# SCH_RMB-Frankenboard_2024-09-02.net
KiCad netlist of a schematic drawn in EasyEDA
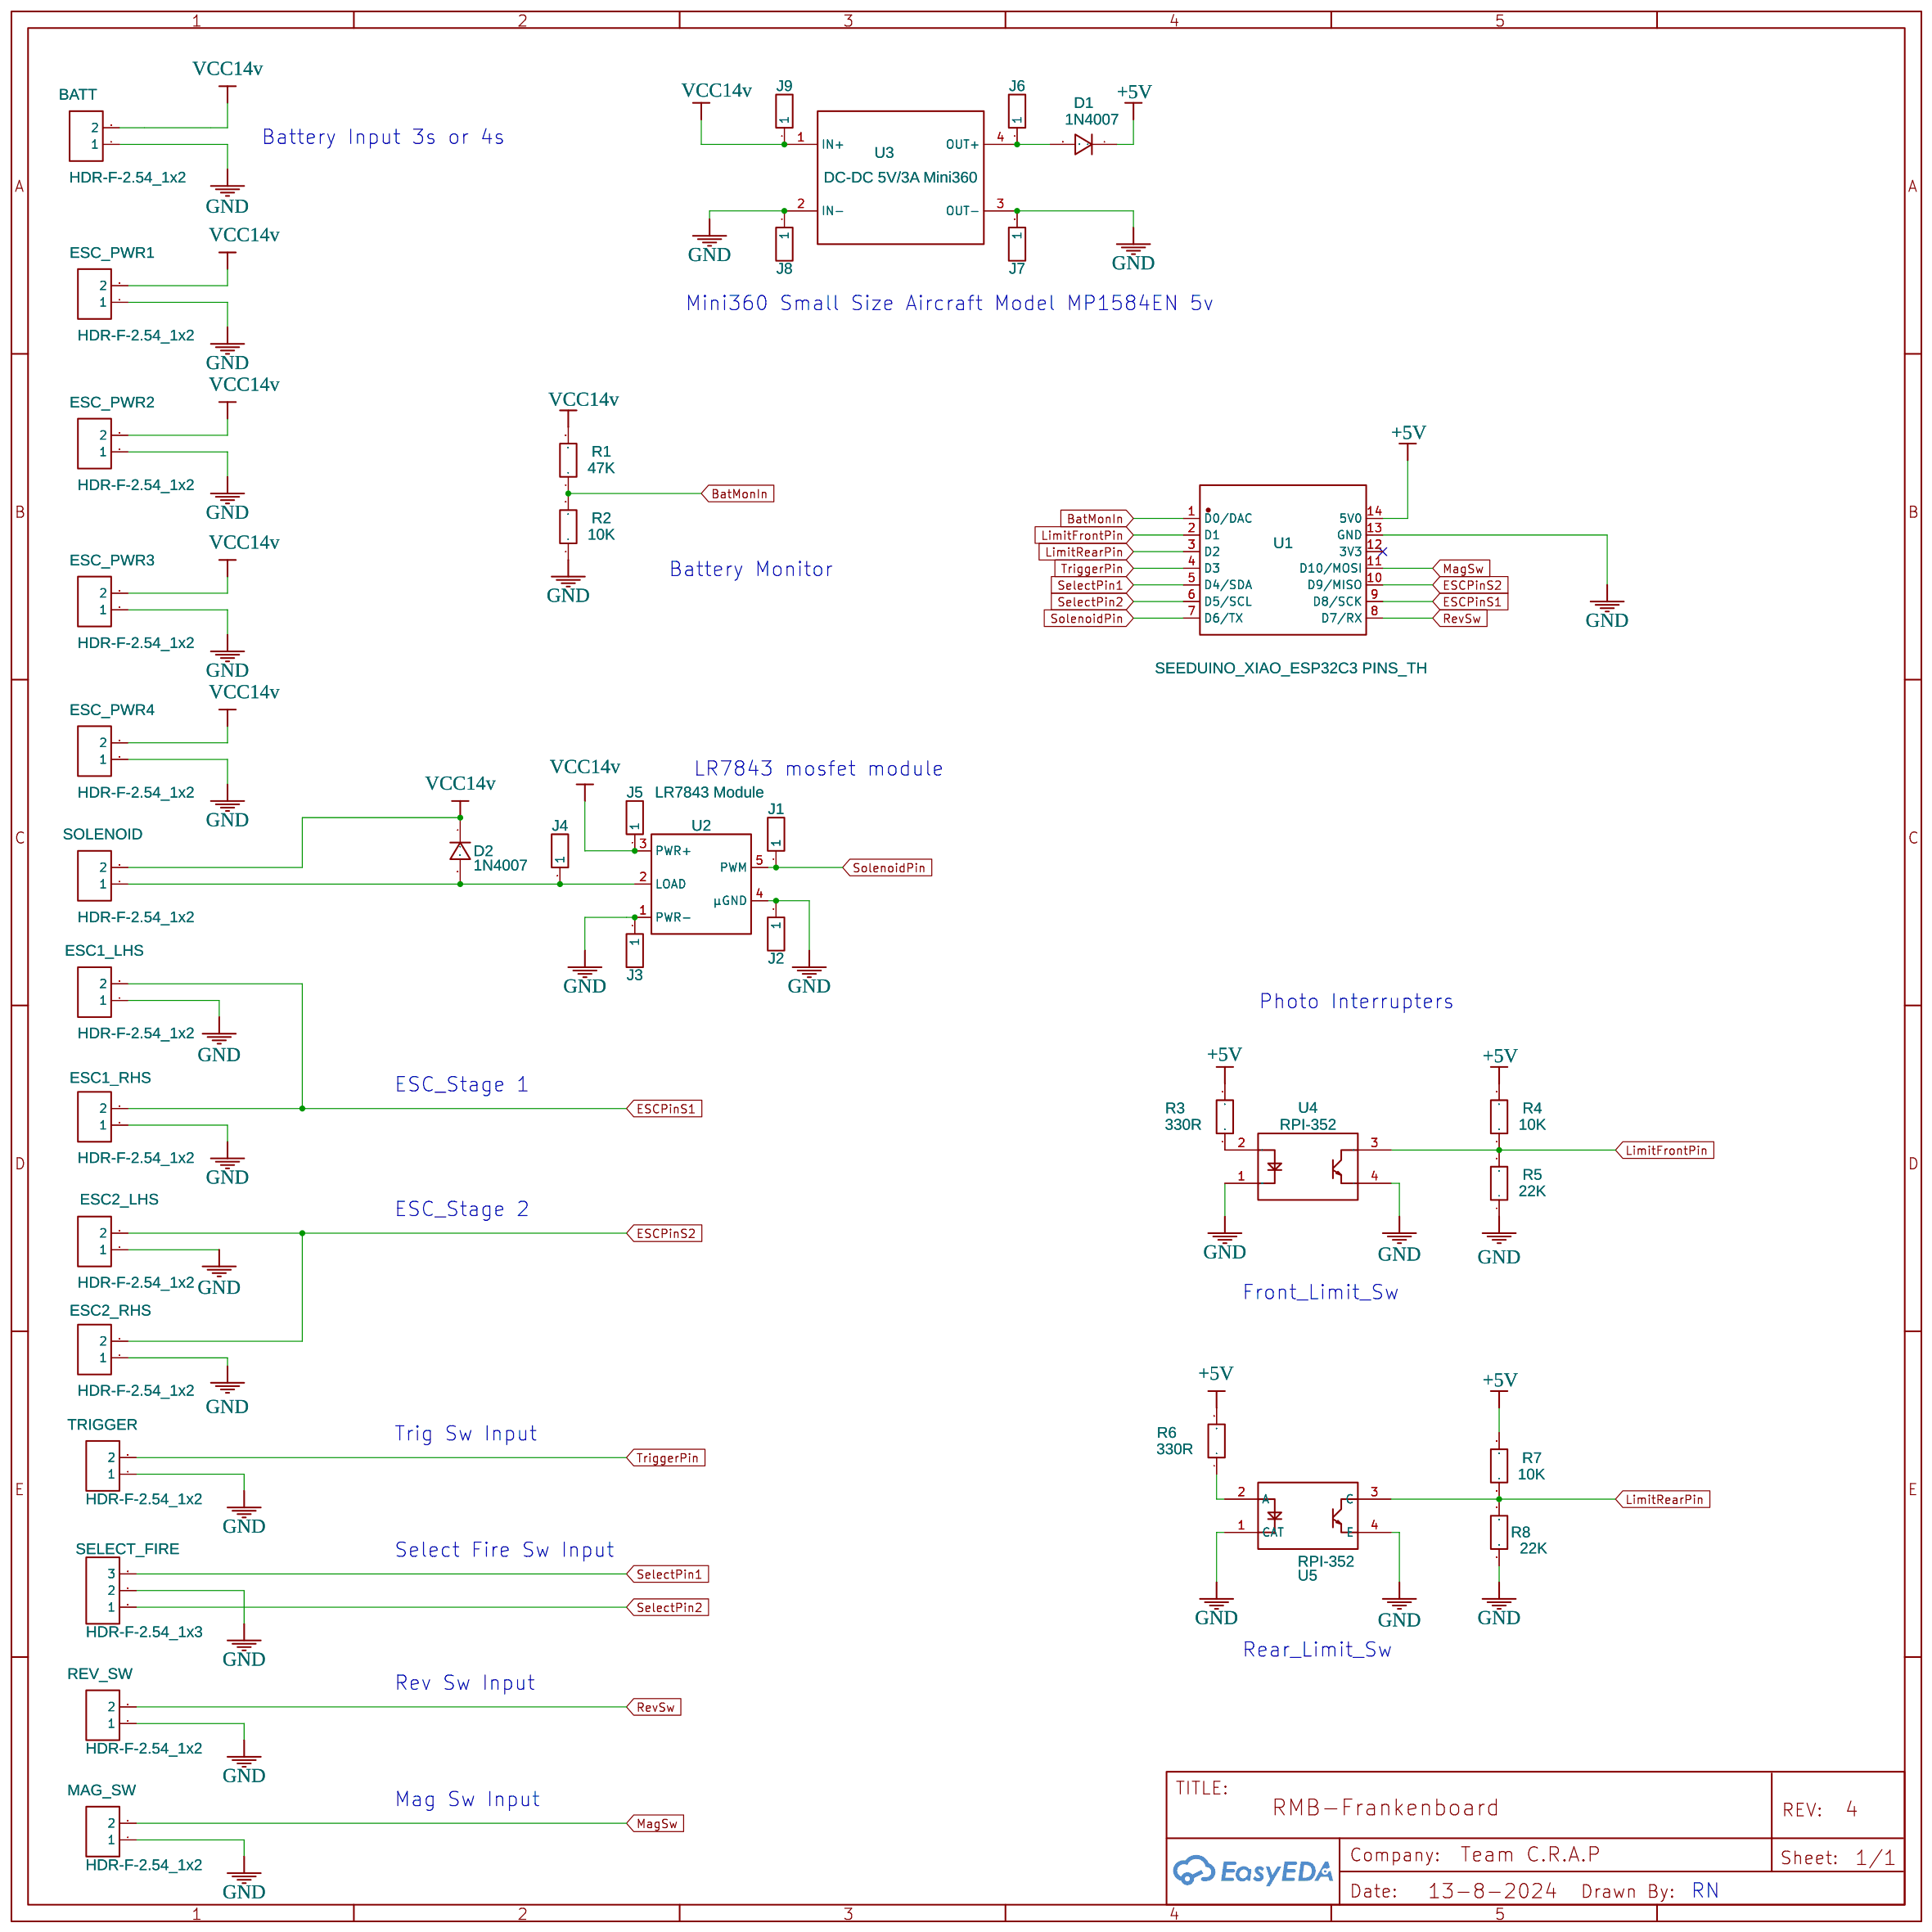
[diagram p0: schematic sheet]

(export (version "E")
  (design (tool "Eeschema 10.0.6"))
  (components
    (comp (ref "BATT") (value "HDR-F-2.54_1x2") (libsource (lib "") (part "HDR-F-2.54_1x2_2")))
    (comp (ref "D1")
      (value "1N4007")
      (fields (field (name "Manufacturer") "SEMTECH"))
      (libsource (lib "") (part "1N4007"))
    )
    (comp (ref "D2")
      (value "1N4007")
      (fields (field (name "Manufacturer") "SEMTECH"))
      (libsource (lib "") (part "1N4007_1"))
    )
    (comp (ref "ESC1_LHS") (value "HDR-F-2.54_1x2") (libsource (lib "") (part "HDR-F-2.54_1x2")))
    (comp (ref "ESC1_RHS") (value "HDR-F-2.54_1x2") (libsource (lib "") (part "HDR-F-2.54_1x2_9")))
    (comp (ref "ESC2_LHS") (value "HDR-F-2.54_1x2") (libsource (lib "") (part "HDR-F-2.54_1x2_7")))
    (comp (ref "ESC2_RHS") (value "HDR-F-2.54_1x2") (libsource (lib "") (part "HDR-F-2.54_1x2_8")))
    (comp (ref "ESC_PWR1") (value "HDR-F-2.54_1x2") (libsource (lib "") (part "HDR-F-2.54_1x2_4")))
    (comp (ref "ESC_PWR2") (value "HDR-F-2.54_1x2") (libsource (lib "") (part "HDR-F-2.54_1x2_4")))
    (comp (ref "ESC_PWR3") (value "HDR-F-2.54_1x2") (libsource (lib "") (part "HDR-F-2.54_1x2_4")))
    (comp (ref "ESC_PWR4") (value "HDR-F-2.54_1x2") (libsource (lib "") (part "HDR-F-2.54_1x2_4")))
    (comp (ref "J1") (value "HDR-M-2.54_1x1") (libsource (lib "") (part "HDR-M-2.54_1x1_1")))
    (comp (ref "J2") (value "HDR-M-2.54_1x1") (libsource (lib "") (part "HDR-M-2.54_1x1")))
    (comp (ref "J3") (value "HDR-M-2.54_1x1") (libsource (lib "") (part "HDR-M-2.54_1x1")))
    (comp (ref "J4") (value "HDR-M-2.54_1x1") (libsource (lib "") (part "HDR-M-2.54_1x1_1")))
    (comp (ref "J5") (value "HDR-M-2.54_1x1") (libsource (lib "") (part "HDR-M-2.54_1x1_1")))
    (comp (ref "J6") (value "HDR-M-2.54_1x1") (libsource (lib "") (part "HDR-M-2.54_1x1_1")))
    (comp (ref "J7") (value "HDR-M-2.54_1x1") (libsource (lib "") (part "HDR-M-2.54_1x1")))
    (comp (ref "J8") (value "HDR-M-2.54_1x1") (libsource (lib "") (part "HDR-M-2.54_1x1")))
    (comp (ref "J9") (value "HDR-M-2.54_1x1") (libsource (lib "") (part "HDR-M-2.54_1x1_1")))
    (comp (ref "MAG_SW") (value "HDR-F-2.54_1x2") (libsource (lib "") (part "HDR-F-2.54_1x2_6")))
    (comp (ref "R1") (value "47K") (libsource (lib "") (part "R_AXIAL-0.3_EU")))
    (comp (ref "R2") (value "10K") (libsource (lib "") (part "R_AXIAL-0.3_EU")))
    (comp (ref "R3") (value "330R") (libsource (lib "") (part "R_AXIAL-0.3_EU")))
    (comp (ref "R4") (value "10K") (libsource (lib "") (part "R_0603_EU")))
    (comp (ref "R5") (value "22K") (libsource (lib "") (part "R_0603_EU")))
    (comp (ref "R6") (value "330R") (libsource (lib "") (part "R_AXIAL-0.3_EU")))
    (comp (ref "R7") (value "10K") (libsource (lib "") (part "R_0603_EU")))
    (comp (ref "R8") (value "22K") (libsource (lib "") (part "R_0603_EU")))
    (comp (ref "REV_SW") (value "HDR-F-2.54_1x2") (libsource (lib "") (part "HDR-F-2.54_1x2_3")))
    (comp (ref "SELECT_FIRE") (value "HDR-F-2.54_1x3") (libsource (lib "") (part "HDR-F-2.54_1x3")))
    (comp (ref "SOLENOID") (value "HDR-F-2.54_1x2") (libsource (lib "") (part "HDR-F-2.54_1x2_1")))
    (comp (ref "TRIGGER") (value "HDR-F-2.54_1x2") (libsource (lib "") (part "HDR-F-2.54_1x2_5")))
    (comp (ref "U1")
      (value "SEEDUINO_XIAO_ESP32C3 PINS_TH")
      (libsource (lib "") (part "SEEDUINO_XIAO_ESP32C3 PINS_TH"))
    )
    (comp (ref "U2") (value "LR7843 Module") (libsource (lib "") (part "LR7843 Module")))
    (comp (ref "U3")
      (value "DC-DC 5V/3A Mini360")
      (fields
        (field (name "Manufacturer Part") "Aircraft Model MP1584EN Power Module")
        (field (name "Manufacturer") "Generic")
      )
      (libsource (lib "") (part "DC-DC 5V/3A Mini360"))
    )
    (comp (ref "U4")
      (value "RPI-352")
      (fields (field (name "Manufacturer") "ROHM(罗姆)"))
      (libsource (lib "") (part "RPI-352"))
    )
    (comp (ref "U5")
      (value "RPI-352")
      (fields (field (name "Manufacturer") "ROHM(罗姆)"))
      (libsource (lib "") (part "RPI-352"))
    )
  )
  (nets
    (net (code "1") (name "+5V") (class "Default")
      (node (ref "D1") (pin "1") (pinfunction "1_1") (pintype "unspecified"))
      (node (ref "R3") (pin "2") (pinfunction "2_2") (pintype "unspecified"))
      (node (ref "R4") (pin "2") (pinfunction "2_2") (pintype "unspecified"))
      (node (ref "R6") (pin "2") (pinfunction "2_2") (pintype "unspecified"))
      (node (ref "R7") (pin "2") (pinfunction "2_2") (pintype "unspecified"))
      (node (ref "U1") (pin "14") (pinfunction "5V0_14") (pintype "unspecified"))
    )
    (net (code "2") (name "BatMonIn") (class "Default")
      (node (ref "R1") (pin "1") (pinfunction "1_1") (pintype "unspecified"))
      (node (ref "R2") (pin "2") (pinfunction "2_2") (pintype "unspecified"))
      (node (ref "U1") (pin "1") (pinfunction "D0/DAC_1") (pintype "unspecified"))
    )
    (net (code "3") (name "ESCPinS1") (class "Default")
      (node (ref "ESC1_LHS") (pin "2") (pinfunction "2_2") (pintype "input"))
      (node (ref "ESC1_RHS") (pin "2") (pinfunction "2_2") (pintype "input"))
      (node (ref "U1") (pin "9") (pinfunction "D8/SCK_9") (pintype "unspecified"))
    )
    (net (code "4") (name "ESCPinS2") (class "Default")
      (node (ref "ESC2_LHS") (pin "2") (pinfunction "2_2") (pintype "input"))
      (node (ref "ESC2_RHS") (pin "2") (pinfunction "2_2") (pintype "input"))
      (node (ref "U1") (pin "10") (pinfunction "D9/MISO_10") (pintype "unspecified"))
    )
    (net (code "5") (name "GND") (class "Default")
      (node (ref "BATT") (pin "1") (pinfunction "1_1") (pintype "input"))
      (node (ref "ESC1_LHS") (pin "1") (pinfunction "1_1") (pintype "input"))
      (node (ref "ESC1_RHS") (pin "1") (pinfunction "1_1") (pintype "input"))
      (node (ref "ESC2_LHS") (pin "1") (pinfunction "1_1") (pintype "input"))
      (node (ref "ESC2_RHS") (pin "1") (pinfunction "1_1") (pintype "input"))
      (node (ref "ESC_PWR1") (pin "1") (pinfunction "1_1") (pintype "input"))
      (node (ref "ESC_PWR2") (pin "1") (pinfunction "1_1") (pintype "input"))
      (node (ref "ESC_PWR3") (pin "1") (pinfunction "1_1") (pintype "input"))
      (node (ref "ESC_PWR4") (pin "1") (pinfunction "1_1") (pintype "input"))
      (node (ref "J2") (pin "1") (pinfunction "1_1") (pintype "input"))
      (node (ref "J3") (pin "1") (pinfunction "1_1") (pintype "input"))
      (node (ref "J7") (pin "1") (pinfunction "1_1") (pintype "input"))
      (node (ref "J8") (pin "1") (pinfunction "1_1") (pintype "input"))
      (node (ref "MAG_SW") (pin "1") (pinfunction "1_1") (pintype "input"))
      (node (ref "R2") (pin "1") (pinfunction "1_1") (pintype "unspecified"))
      (node (ref "R5") (pin "1") (pinfunction "1_1") (pintype "unspecified"))
      (node (ref "R8") (pin "1") (pinfunction "1_1") (pintype "unspecified"))
      (node (ref "REV_SW") (pin "1") (pinfunction "1_1") (pintype "input"))
      (node (ref "SELECT_FIRE") (pin "2") (pinfunction "2_2") (pintype "input"))
      (node (ref "TRIGGER") (pin "1") (pinfunction "1_1") (pintype "input"))
      (node (ref "U1") (pin "13") (pinfunction "GND_13") (pintype "unspecified"))
      (node (ref "U2") (pin "1") (pinfunction "PWR-_1") (pintype "unspecified"))
      (node (ref "U2") (pin "4") (pinfunction "μGND_4") (pintype "unspecified"))
      (node (ref "U3") (pin "2") (pinfunction "IN-_2") (pintype "unspecified"))
      (node (ref "U3") (pin "3") (pinfunction "OUT-_3") (pintype "unspecified"))
      (node (ref "U4") (pin "1") (pinfunction "CAT_1") (pintype "unspecified"))
      (node (ref "U4") (pin "4") (pinfunction "E_4") (pintype "unspecified"))
      (node (ref "U5") (pin "1") (pinfunction "CAT_1") (pintype "unspecified"))
      (node (ref "U5") (pin "4") (pinfunction "E_4") (pintype "unspecified"))
    )
    (net (code "6") (name "LimitFrontPin") (class "Default")
      (node (ref "R4") (pin "1") (pinfunction "1_1") (pintype "unspecified"))
      (node (ref "R5") (pin "2") (pinfunction "2_2") (pintype "unspecified"))
      (node (ref "U1") (pin "2") (pinfunction "D1_2") (pintype "unspecified"))
      (node (ref "U4") (pin "3") (pinfunction "C_3") (pintype "unspecified"))
    )
    (net (code "7") (name "LimitRearPin") (class "Default")
      (node (ref "R7") (pin "1") (pinfunction "1_1") (pintype "unspecified"))
      (node (ref "R8") (pin "2") (pinfunction "2_2") (pintype "unspecified"))
      (node (ref "U1") (pin "3") (pinfunction "D2_3") (pintype "unspecified"))
      (node (ref "U5") (pin "3") (pinfunction "C_3") (pintype "unspecified"))
    )
    (net (code "8") (name "MagSw") (class "Default")
      (node (ref "MAG_SW") (pin "2") (pinfunction "2_2") (pintype "input"))
      (node (ref "U1") (pin "11") (pinfunction "D10/MOSI_11") (pintype "unspecified"))
    )
    (net (code "9") (name "Net-(U2-LOAD)") (class "Default")
      (node (ref "D2") (pin "2") (pinfunction "2_2") (pintype "unspecified"))
      (node (ref "J4") (pin "1") (pinfunction "1_1") (pintype "input"))
      (node (ref "SOLENOID") (pin "1") (pinfunction "1_1") (pintype "input"))
      (node (ref "U2") (pin "2") (pinfunction "LOAD_2") (pintype "unspecified"))
    )
    (net (code "10") (name "Net-(U3-OUT+)") (class "Default")
      (node (ref "D1") (pin "2") (pinfunction "2_2") (pintype "unspecified"))
      (node (ref "J6") (pin "1") (pinfunction "1_1") (pintype "input"))
      (node (ref "U3") (pin "4") (pinfunction "OUT+_4") (pintype "unspecified"))
    )
    (net (code "11") (name "Net-(U4-A)") (class "Default")
      (node (ref "R3") (pin "1") (pinfunction "1_1") (pintype "unspecified"))
      (node (ref "U4") (pin "2") (pinfunction "A_2") (pintype "unspecified"))
    )
    (net (code "12") (name "Net-(U5-A)") (class "Default")
      (node (ref "R6") (pin "1") (pinfunction "1_1") (pintype "unspecified"))
      (node (ref "U5") (pin "2") (pinfunction "A_2") (pintype "unspecified"))
    )
    (net (code "13") (name "RevSw") (class "Default")
      (node (ref "REV_SW") (pin "2") (pinfunction "2_2") (pintype "input"))
      (node (ref "U1") (pin "8") (pinfunction "D7/RX_8") (pintype "unspecified"))
    )
    (net (code "14") (name "SelectPin1") (class "Default")
      (node (ref "SELECT_FIRE") (pin "3") (pinfunction "3_3") (pintype "input"))
      (node (ref "U1") (pin "5") (pinfunction "D4/SDA_5") (pintype "unspecified"))
    )
    (net (code "15") (name "SelectPin2") (class "Default")
      (node (ref "SELECT_FIRE") (pin "1") (pinfunction "1_1") (pintype "input"))
      (node (ref "U1") (pin "6") (pinfunction "D5/SCL_6") (pintype "unspecified"))
    )
    (net (code "16") (name "SolenoidPin") (class "Default")
      (node (ref "J1") (pin "1") (pinfunction "1_1") (pintype "input"))
      (node (ref "U1") (pin "7") (pinfunction "D6/TX_7") (pintype "unspecified"))
      (node (ref "U2") (pin "5") (pinfunction "PWM_5") (pintype "unspecified"))
    )
    (net (code "17") (name "TriggerPin") (class "Default")
      (node (ref "TRIGGER") (pin "2") (pinfunction "2_2") (pintype "input"))
      (node (ref "U1") (pin "4") (pinfunction "D3_4") (pintype "unspecified"))
    )
    (net (code "18") (name "VCC14v") (class "Default")
      (node (ref "BATT") (pin "2") (pinfunction "2_2") (pintype "input"))
      (node (ref "D2") (pin "1") (pinfunction "1_1") (pintype "unspecified"))
      (node (ref "ESC_PWR1") (pin "2") (pinfunction "2_2") (pintype "input"))
      (node (ref "ESC_PWR2") (pin "2") (pinfunction "2_2") (pintype "input"))
      (node (ref "ESC_PWR3") (pin "2") (pinfunction "2_2") (pintype "input"))
      (node (ref "ESC_PWR4") (pin "2") (pinfunction "2_2") (pintype "input"))
      (node (ref "J5") (pin "1") (pinfunction "1_1") (pintype "input"))
      (node (ref "J9") (pin "1") (pinfunction "1_1") (pintype "input"))
      (node (ref "R1") (pin "2") (pinfunction "2_2") (pintype "unspecified"))
      (node (ref "SOLENOID") (pin "2") (pinfunction "2_2") (pintype "input"))
      (node (ref "U2") (pin "3") (pinfunction "PWR+_3") (pintype "unspecified"))
      (node (ref "U3") (pin "1") (pinfunction "IN+_1") (pintype "unspecified"))
    )
    (net (code "19") (name "unconnected-(U1-3V3-Pad12)") (class "Default")
      (node (ref "U1") (pin "12") (pinfunction "3V3_12") (pintype "unspecified+no_connect"))
    )
  )
)
